# Laser_Monitor.net
KiCad netlist of a schematic drawn in EAGLE
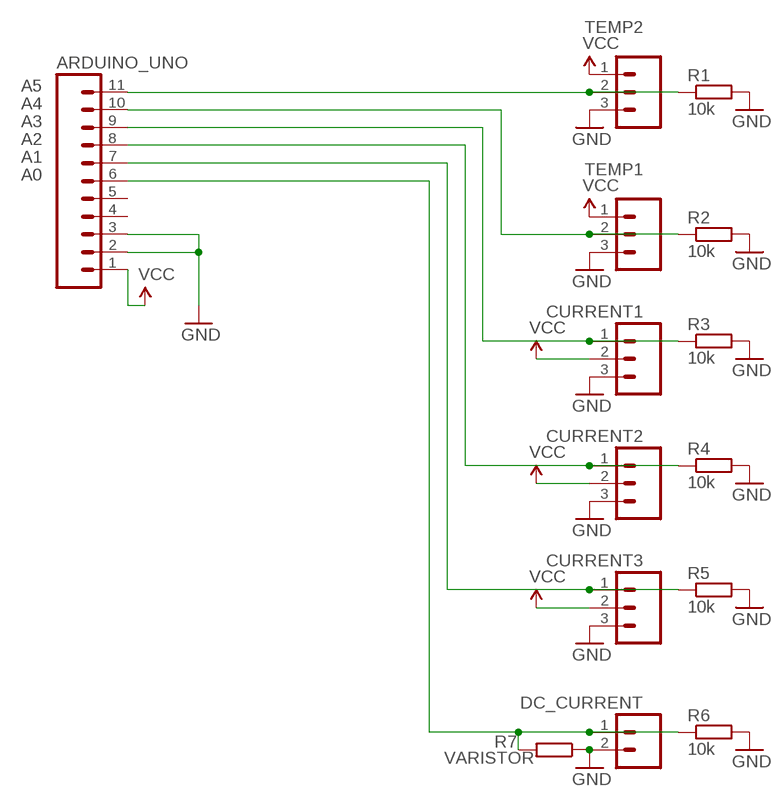
[diagram p0: schematic, sheet 1]

(export (version "E")
  (design (tool "Eeschema 10.0.6"))
  (components
    (comp (ref "ARDUINO_UNO")
      (value "M11PTH")
      (footprint "eagle-import:1X11")
      (libsource (lib "eagle-import") (part "M11PTH"))
    )
    (comp (ref "CURRENT1")
      (value "M03PTH")
      (footprint "eagle-import:1X03")
      (libsource (lib "eagle-import") (part "M03PTH"))
    )
    (comp (ref "CURRENT2")
      (value "M03PTH")
      (footprint "eagle-import:1X03")
      (libsource (lib "eagle-import") (part "M03PTH"))
    )
    (comp (ref "CURRENT3")
      (value "M03PTH")
      (footprint "eagle-import:1X03")
      (libsource (lib "eagle-import") (part "M03PTH"))
    )
    (comp (ref "DC_CURRENT")
      (value "M02PTH")
      (footprint "eagle-import:1X02")
      (libsource (lib "eagle-import") (part "M02PTH"))
    )
    (comp (ref "R1")
      (value "10k")
      (footprint "eagle-import:0204V")
      (libsource (lib "eagle-import") (part "R-EU_0204/2V"))
    )
    (comp (ref "R2")
      (value "10k")
      (footprint "eagle-import:0204V")
      (libsource (lib "eagle-import") (part "R-EU_0204/2V"))
    )
    (comp (ref "R3")
      (value "10k")
      (footprint "eagle-import:0204V")
      (libsource (lib "eagle-import") (part "R-EU_0204/2V"))
    )
    (comp (ref "R4")
      (value "10k")
      (footprint "eagle-import:0204V")
      (libsource (lib "eagle-import") (part "R-EU_0204/2V"))
    )
    (comp (ref "R5")
      (value "10k")
      (footprint "eagle-import:0204V")
      (libsource (lib "eagle-import") (part "R-EU_0204/2V"))
    )
    (comp (ref "R6")
      (value "10k")
      (footprint "eagle-import:0204V")
      (libsource (lib "eagle-import") (part "R-EU_0204/2V"))
    )
    (comp (ref "R7")
      (value "VARISTOR")
      (footprint "eagle-import:P0817V")
      (libsource (lib "eagle-import") (part "R-EU_0817/7V"))
    )
    (comp (ref "TEMP1")
      (value "M03PTH")
      (footprint "eagle-import:1X03")
      (libsource (lib "eagle-import") (part "M03PTH"))
    )
    (comp (ref "TEMP2")
      (value "M03PTH")
      (footprint "eagle-import:1X03")
      (libsource (lib "eagle-import") (part "M03PTH"))
    )
  )
  (nets
    (net (code "1") (name "/A0") (class "Default")
      (node (ref "ARDUINO_UNO") (pin "6") (pinfunction "6_6") (pintype "passive"))
      (node (ref "DC_CURRENT") (pin "1") (pinfunction "1_1") (pintype "passive"))
      (node (ref "R6") (pin "1") (pinfunction "1_1") (pintype "passive"))
      (node (ref "R7") (pin "2") (pinfunction "2_2") (pintype "passive"))
    )
    (net (code "2") (name "/A1") (class "Default")
      (node (ref "ARDUINO_UNO") (pin "7") (pinfunction "7_7") (pintype "passive"))
      (node (ref "CURRENT3") (pin "1") (pinfunction "1_1") (pintype "passive"))
      (node (ref "R5") (pin "1") (pinfunction "1_1") (pintype "passive"))
    )
    (net (code "3") (name "/A2") (class "Default")
      (node (ref "ARDUINO_UNO") (pin "8") (pinfunction "8_8") (pintype "passive"))
      (node (ref "CURRENT2") (pin "1") (pinfunction "1_1") (pintype "passive"))
      (node (ref "R4") (pin "1") (pinfunction "1_1") (pintype "passive"))
    )
    (net (code "4") (name "/A3") (class "Default")
      (node (ref "ARDUINO_UNO") (pin "9") (pinfunction "9_9") (pintype "passive"))
      (node (ref "CURRENT1") (pin "1") (pinfunction "1_1") (pintype "passive"))
      (node (ref "R3") (pin "1") (pinfunction "1_1") (pintype "passive"))
    )
    (net (code "5") (name "/A4") (class "Default")
      (node (ref "ARDUINO_UNO") (pin "10") (pinfunction "10_10") (pintype "passive"))
      (node (ref "R2") (pin "1") (pinfunction "1_1") (pintype "passive"))
      (node (ref "TEMP1") (pin "2") (pinfunction "2_2") (pintype "passive"))
    )
    (net (code "6") (name "/A5") (class "Default")
      (node (ref "ARDUINO_UNO") (pin "11") (pinfunction "11_11") (pintype "passive"))
      (node (ref "R1") (pin "1") (pinfunction "1_1") (pintype "passive"))
      (node (ref "TEMP2") (pin "2") (pinfunction "2_2") (pintype "passive"))
    )
    (net (code "7") (name "GND") (class "Default")
      (node (ref "ARDUINO_UNO") (pin "2") (pinfunction "2_2") (pintype "passive"))
      (node (ref "ARDUINO_UNO") (pin "3") (pinfunction "3_3") (pintype "passive"))
      (node (ref "CURRENT1") (pin "3") (pinfunction "3_3") (pintype "passive"))
      (node (ref "CURRENT2") (pin "3") (pinfunction "3_3") (pintype "passive"))
      (node (ref "CURRENT3") (pin "3") (pinfunction "3_3") (pintype "passive"))
      (node (ref "DC_CURRENT") (pin "2") (pinfunction "2_2") (pintype "passive"))
      (node (ref "R1") (pin "2") (pinfunction "2_2") (pintype "passive"))
      (node (ref "R2") (pin "2") (pinfunction "2_2") (pintype "passive"))
      (node (ref "R3") (pin "2") (pinfunction "2_2") (pintype "passive"))
      (node (ref "R4") (pin "2") (pinfunction "2_2") (pintype "passive"))
      (node (ref "R5") (pin "2") (pinfunction "2_2") (pintype "passive"))
      (node (ref "R6") (pin "2") (pinfunction "2_2") (pintype "passive"))
      (node (ref "R7") (pin "1") (pinfunction "1_1") (pintype "passive"))
      (node (ref "TEMP1") (pin "3") (pinfunction "3_3") (pintype "passive"))
      (node (ref "TEMP2") (pin "3") (pinfunction "3_3") (pintype "passive"))
    )
    (net (code "8") (name "VCC") (class "Default")
      (node (ref "ARDUINO_UNO") (pin "1") (pinfunction "1_1") (pintype "passive"))
      (node (ref "CURRENT1") (pin "2") (pinfunction "2_2") (pintype "passive"))
      (node (ref "CURRENT2") (pin "2") (pinfunction "2_2") (pintype "passive"))
      (node (ref "CURRENT3") (pin "2") (pinfunction "2_2") (pintype "passive"))
      (node (ref "TEMP1") (pin "1") (pinfunction "1_1") (pintype "passive"))
      (node (ref "TEMP2") (pin "1") (pinfunction "1_1") (pintype "passive"))
    )
    (net (code "9") (name "unconnected-(ARDUINO_UNO-Pad4)") (class "Default")
      (node (ref "ARDUINO_UNO") (pin "4") (pinfunction "4_4") (pintype "passive"))
    )
    (net (code "10") (name "unconnected-(ARDUINO_UNO-Pad5)") (class "Default")
      (node (ref "ARDUINO_UNO") (pin "5") (pinfunction "5_5") (pintype "passive"))
    )
  )
)
